# lamloei_node32s3wroom_ft231xq_main_2laye.net
KiCad netlist of a schematic drawn in EAGLE
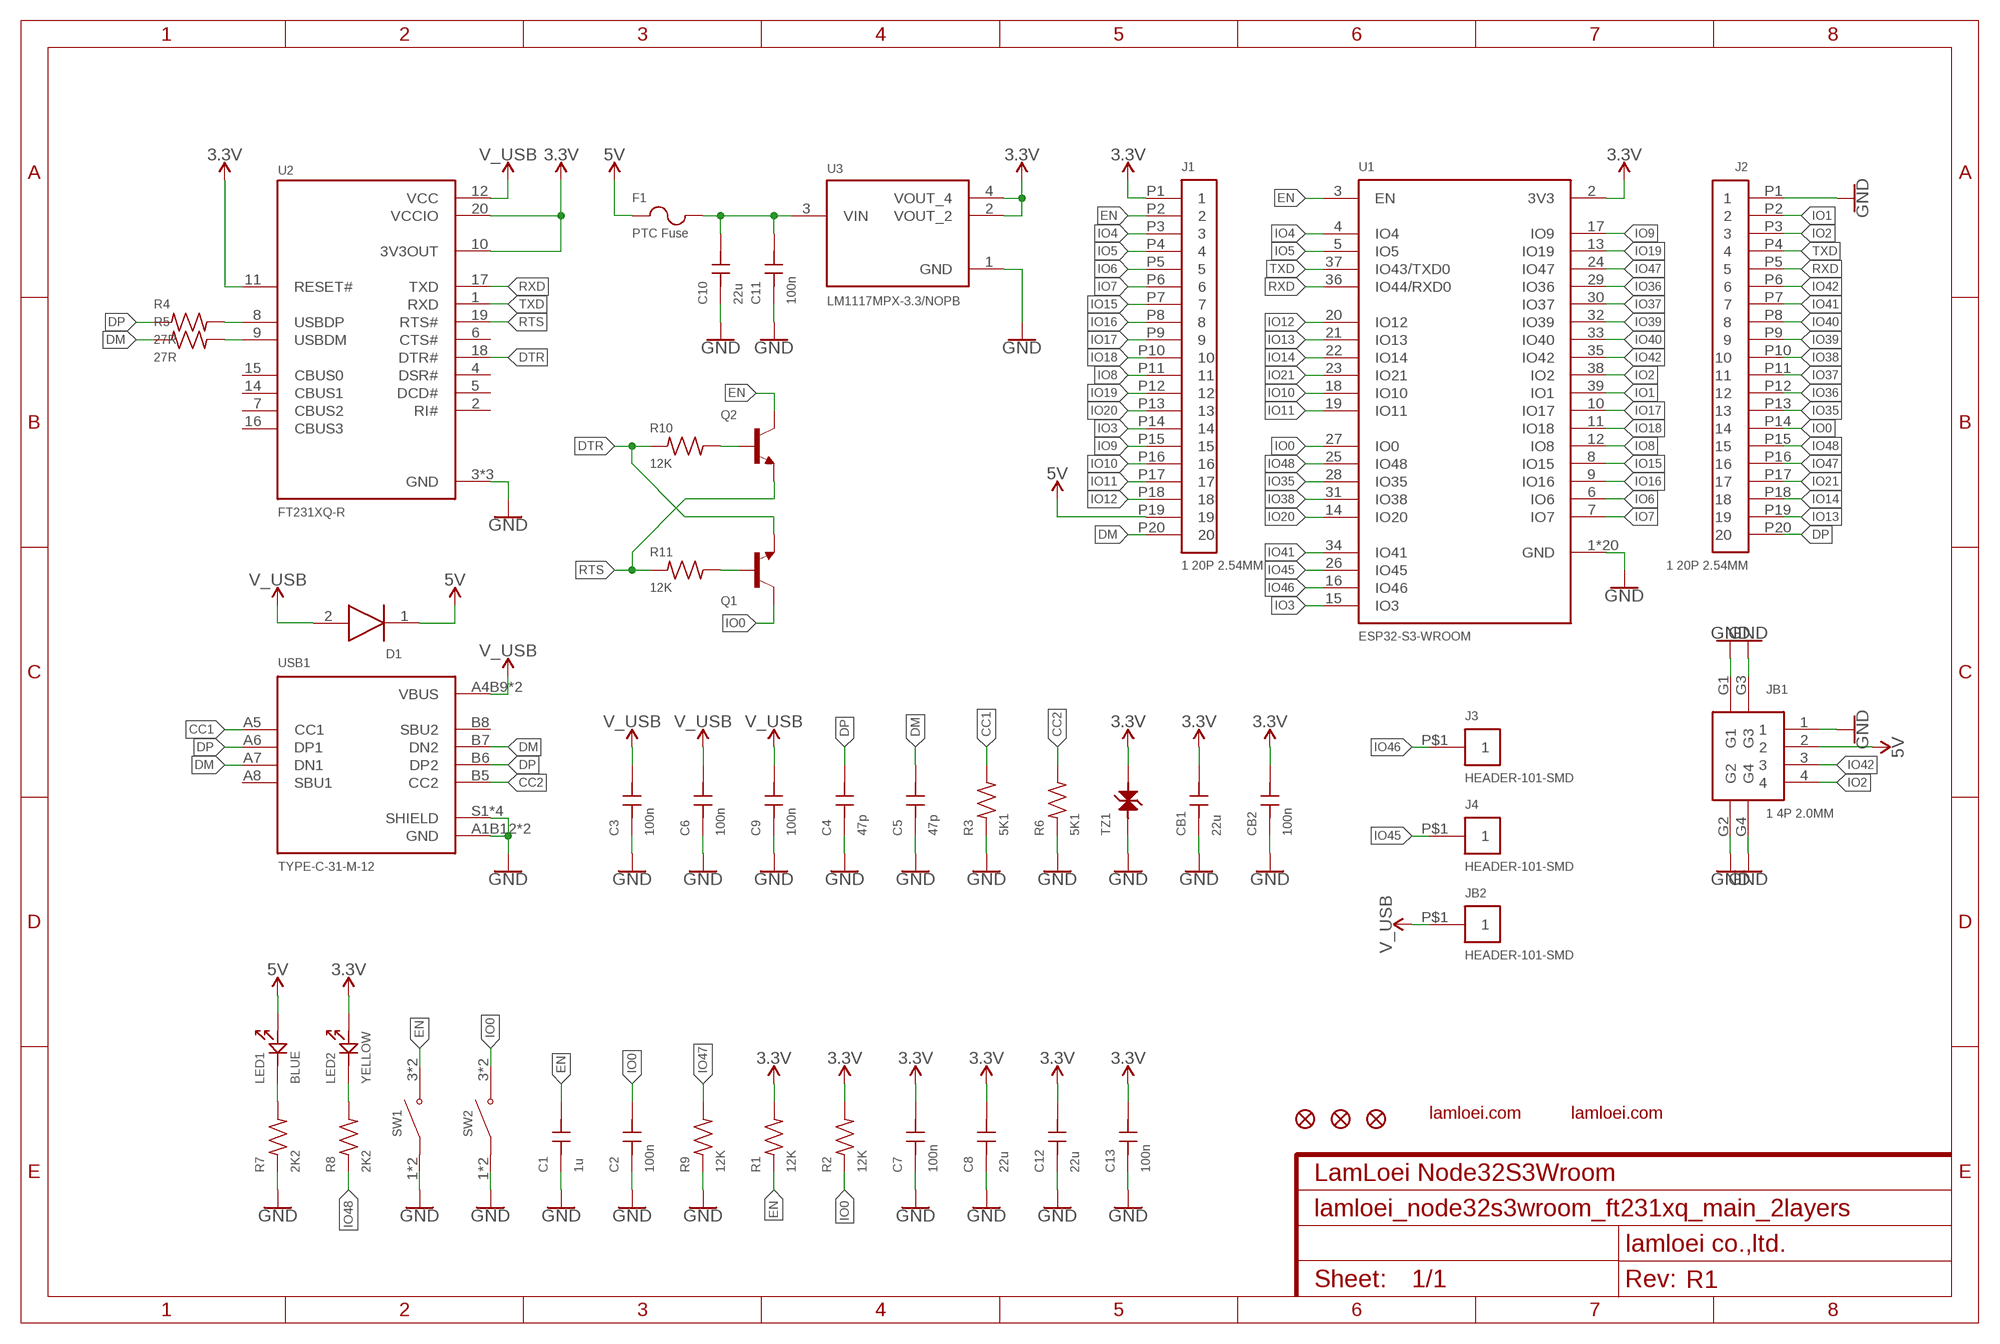
[diagram p0: schematic, sheet 1]

(export (version "E")
  (design (tool "Eeschema 10.0.6"))
  (components
    (comp (ref "C1")
      (value "1u")
      (footprint "eagle-import:GRM155R70J105KA12D")
      (fields (field (name "MANUFACTURER_PART_NUMBER") "GRM155R70J105KA12D"))
      (libsource (lib "eagle-import") (part "GRM155R70J105KA12D"))
    )
    (comp (ref "C2")
      (value "100n")
      (footprint "eagle-import:GCM155R71H104KE02D")
      (fields (field (name "MANUFACTURER_PART_NUMBER") "GCM155R71H104KE02D"))
      (libsource (lib "eagle-import") (part "GCM155R71H104KE02D"))
    )
    (comp (ref "C3")
      (value "100n")
      (footprint "eagle-import:GCM155R71H104KE02D")
      (fields (field (name "MANUFACTURER_PART_NUMBER") "GCM155R71H104KE02D"))
      (libsource (lib "eagle-import") (part "GCM155R71H104KE02D"))
    )
    (comp (ref "C4")
      (value "47p")
      (footprint "eagle-import:GCM1555C1H470JA16D")
      (fields (field (name "MANUFACTURER_PART_NUMBER") "GCM1555C1H470JA16D"))
      (libsource (lib "eagle-import") (part "GCM1555C1H470JA16D"))
    )
    (comp (ref "C5")
      (value "47p")
      (footprint "eagle-import:GCM1555C1H470JA16D")
      (fields (field (name "MANUFACTURER_PART_NUMBER") "GCM1555C1H470JA16D"))
      (libsource (lib "eagle-import") (part "GCM1555C1H470JA16D"))
    )
    (comp (ref "C6")
      (value "100n")
      (footprint "eagle-import:GCM155R71H104KE02D")
      (fields (field (name "MANUFACTURER_PART_NUMBER") "GCM155R71H104KE02D"))
      (libsource (lib "eagle-import") (part "GCM155R71H104KE02D"))
    )
    (comp (ref "C7")
      (value "100n")
      (footprint "eagle-import:GCM155R71H104KE02D")
      (fields (field (name "MANUFACTURER_PART_NUMBER") "GCM155R71H104KE02D"))
      (libsource (lib "eagle-import") (part "GCM155R71H104KE02D"))
    )
    (comp (ref "C8")
      (value "22u")
      (footprint "eagle-import:GCM21BR71H105KA03L")
      (fields (field (name "MANUFACTURER_PART_NUMBER") "GCM21BR71H105KA03L"))
      (libsource (lib "eagle-import") (part "GCM21BR71H105KA03L"))
    )
    (comp (ref "C9")
      (value "100n")
      (footprint "eagle-import:GCM155R71H104KE02D")
      (fields (field (name "MANUFACTURER_PART_NUMBER") "GCM155R71H104KE02D"))
      (libsource (lib "eagle-import") (part "GCM155R71H104KE02D"))
    )
    (comp (ref "C10")
      (value "22u")
      (footprint "eagle-import:GCM21BR71H105KA03L")
      (fields (field (name "MANUFACTURER_PART_NUMBER") "GCM21BR71H105KA03L"))
      (libsource (lib "eagle-import") (part "GCM21BR71H105KA03L"))
    )
    (comp (ref "C11")
      (value "100n")
      (footprint "eagle-import:GCM155R71H104KE02D")
      (fields (field (name "MANUFACTURER_PART_NUMBER") "GCM155R71H104KE02D"))
      (libsource (lib "eagle-import") (part "GCM155R71H104KE02D"))
    )
    (comp (ref "C12")
      (value "22u")
      (footprint "eagle-import:GCM21BR71H105KA03L")
      (fields (field (name "MANUFACTURER_PART_NUMBER") "GCM21BR71H105KA03L"))
      (libsource (lib "eagle-import") (part "GCM21BR71H105KA03L"))
    )
    (comp (ref "C13")
      (value "100n")
      (footprint "eagle-import:GCM155R71H104KE02D")
      (fields (field (name "MANUFACTURER_PART_NUMBER") "GCM155R71H104KE02D"))
      (libsource (lib "eagle-import") (part "GCM155R71H104KE02D"))
    )
    (comp (ref "CB1")
      (value "22u")
      (footprint "eagle-import:GCM21BR71H105KA03L")
      (fields (field (name "MANUFACTURER_PART_NUMBER") "GCM21BR71H105KA03L"))
      (libsource (lib "eagle-import") (part "GCM21BR71H105KA03L"))
    )
    (comp (ref "CB2")
      (value "100n")
      (footprint "eagle-import:GCM155R71H104KE02D")
      (fields (field (name "MANUFACTURER_PART_NUMBER") "GCM155R71H104KE02D"))
      (libsource (lib "eagle-import") (part "GCM155R71H104KE02D"))
    )
    (comp (ref "D1")
      (value "PMEG4050EP,115")
      (footprint "eagle-import:PMEG4050EP,115")
      (fields (field (name "RS_PART_NUMBER") "7805405P"))
      (libsource (lib "eagle-import") (part "PMEG4050EP,115"))
    )
    (comp (ref "F1")
      (value "PTC Fuse")
      (footprint "eagle-import:MF-NSMF050-2")
      (fields
        (field (name "LCSC_PART") "C75464")
        (field (name "MANUFACTURER") "BOURNS")
        (field (name "MANUFACTURER_PART_NUMBER") "MF-NSMF050-2")
      )
      (libsource (lib "eagle-import") (part "MF-NSMF050-2"))
    )
    (comp (ref "J1")
      (value "1 20P 2.54MM")
      (footprint "eagle-import:HEADER-120")
      (libsource (lib "eagle-import") (part "HEADER-120"))
    )
    (comp (ref "J2")
      (value "1 20P 2.54MM")
      (footprint "eagle-import:HEADER-120")
      (libsource (lib "eagle-import") (part "lamloei_e77_HEADER-120B_HEADER-120"))
    )
    (comp (ref "J3")
      (value "HEADER-101-SMD")
      (footprint "eagle-import:HEADER-101-SMD")
      (libsource (lib "eagle-import") (part "HEADER-101-SMD"))
    )
    (comp (ref "J4")
      (value "HEADER-101-SMD")
      (footprint "eagle-import:HEADER-101-SMD")
      (libsource (lib "eagle-import") (part "HEADER-101-SMD"))
    )
    (comp (ref "JB1")
      (value "1 4P 2.0MM")
      (footprint "eagle-import:A2012WR-S-4P")
      (libsource (lib "eagle-import") (part "A2012WR-S-4P"))
    )
    (comp (ref "JB2")
      (value "HEADER-101-SMD")
      (footprint "eagle-import:HEADER-101-SMD")
      (libsource (lib "eagle-import") (part "HEADER-101-SMD"))
    )
    (comp (ref "LED1")
      (value "BLUE")
      (footprint "eagle-import:19-217BHC-ZL1M2RY3T")
      (fields (field (name "MANUFACTURER_PART_NUMBER") "19-217BHC-ZL1M2RY3T"))
      (libsource (lib "eagle-import") (part "19-217BHC-ZL1M2RY3T"))
    )
    (comp (ref "LED2")
      (value "YELLOW")
      (footprint "eagle-import:19-213_Y2C-CQ2R2L_3T(CY)")
      (fields (field (name "MANUFACTURER_PART_NUMBER") "19-213/Y2C-CQ2R2L/3T(CY)"))
      (libsource (lib "eagle-import") (part "19-213/Y2C-CQ2R2L/3T(CY)"))
    )
    (comp (ref "Q1")
      (value "BC847B,215")
      (footprint "eagle-import:BC847B,215")
      (fields (field (name "MF") "ON Semiconductor") (field (name "MP") "BC847BLT3G"))
      (libsource (lib "eagle-import") (part "BC847B,215"))
    )
    (comp (ref "Q2")
      (value "BC847B,215")
      (footprint "eagle-import:BC847B,215")
      (fields (field (name "MF") "ON Semiconductor") (field (name "MP") "BC847BLT3G"))
      (libsource (lib "eagle-import") (part "BC847B,215"))
    )
    (comp (ref "R1")
      (value "12K")
      (footprint "eagle-import:R0402")
      (fields
        (field (name "LCSC_PART") "C114760")
        (field (name "MANUFACTURER") "YAGEO")
        (field (name "MANUFACTURER_PART_NUMBER") "RC0402FR-0712KL")
      )
      (libsource (lib "eagle-import") (part "RC0402FR-0712KL"))
    )
    (comp (ref "R2")
      (value "12K")
      (footprint "eagle-import:R0402")
      (fields
        (field (name "LCSC_PART") "C114760")
        (field (name "MANUFACTURER") "YAGEO")
        (field (name "MANUFACTURER_PART_NUMBER") "RC0402FR-0712KL")
      )
      (libsource (lib "eagle-import") (part "RC0402FR-0712KL"))
    )
    (comp (ref "R3")
      (value "5K1")
      (footprint "eagle-import:R0402")
      (fields
        (field (name "LCSC_PART") "C105872")
        (field (name "MANUFACTURER") "YAGEO")
        (field (name "MANUFACTURER_PART_NUMBER") "RC0402FR-075K1L")
      )
      (libsource (lib "eagle-import") (part "RC0402FR-075K1L"))
    )
    (comp (ref "R4")
      (value "27R")
      (footprint "eagle-import:R0402")
      (fields
        (field (name "LCSC_PART") "C138021")
        (field (name "MANUFACTURER") "YAGEO")
        (field (name "MANUFACTURER_PART_NUMBER") "RC0402FR-0727RL")
      )
      (libsource (lib "eagle-import") (part "RC0402FR-0727RL"))
    )
    (comp (ref "R5")
      (value "27R")
      (footprint "eagle-import:R0402")
      (fields
        (field (name "LCSC_PART") "C138021")
        (field (name "MANUFACTURER") "YAGEO")
        (field (name "MANUFACTURER_PART_NUMBER") "RC0402FR-0727RL")
      )
      (libsource (lib "eagle-import") (part "RC0402FR-0727RL"))
    )
    (comp (ref "R6")
      (value "5K1")
      (footprint "eagle-import:R0402")
      (fields
        (field (name "LCSC_PART") "C105872")
        (field (name "MANUFACTURER") "YAGEO")
        (field (name "MANUFACTURER_PART_NUMBER") "RC0402FR-075K1L")
      )
      (libsource (lib "eagle-import") (part "RC0402FR-075K1L"))
    )
    (comp (ref "R7")
      (value "2K2")
      (footprint "eagle-import:R0402")
      (fields
        (field (name "LCSC_PART") "C114762")
        (field (name "MANUFACTURER") "YAGEO")
        (field (name "MANUFACTURER_PART_NUMBER") "RC0402FR-072K2L")
      )
      (libsource (lib "eagle-import") (part "RC0402FR-072K2L"))
    )
    (comp (ref "R8")
      (value "2K2")
      (footprint "eagle-import:R0402")
      (fields
        (field (name "LCSC_PART") "C114762")
        (field (name "MANUFACTURER") "YAGEO")
        (field (name "MANUFACTURER_PART_NUMBER") "RC0402FR-072K2L")
      )
      (libsource (lib "eagle-import") (part "RC0402FR-072K2L"))
    )
    (comp (ref "R9")
      (value "12K")
      (footprint "eagle-import:R0402")
      (fields
        (field (name "LCSC_PART") "C114760")
        (field (name "MANUFACTURER") "YAGEO")
        (field (name "MANUFACTURER_PART_NUMBER") "RC0402FR-0712KL")
      )
      (libsource (lib "eagle-import") (part "RC0402FR-0712KL"))
    )
    (comp (ref "R10")
      (value "12K")
      (footprint "eagle-import:R0402")
      (fields
        (field (name "LCSC_PART") "C114760")
        (field (name "MANUFACTURER") "YAGEO")
        (field (name "MANUFACTURER_PART_NUMBER") "RC0402FR-0712KL")
      )
      (libsource (lib "eagle-import") (part "RC0402FR-0712KL"))
    )
    (comp (ref "R11")
      (value "12K")
      (footprint "eagle-import:R0402")
      (fields
        (field (name "LCSC_PART") "C114760")
        (field (name "MANUFACTURER") "YAGEO")
        (field (name "MANUFACTURER_PART_NUMBER") "RC0402FR-0712KL")
      )
      (libsource (lib "eagle-import") (part "RC0402FR-0712KL"))
    )
    (comp (ref "SW1")
      (value "K2-1808SN-A4SW-01")
      (footprint "eagle-import:K2-1808SN-A4SW-01")
      (fields (field (name "COMMENT") "4-1437565-2") (field (name "MF") "TE Connectivity"))
      (libsource (lib "eagle-import") (part "K2-1808SN-A4SW-01"))
    )
    (comp (ref "SW2")
      (value "K2-1808SN-A4SW-01")
      (footprint "eagle-import:K2-1808SN-A4SW-01")
      (fields (field (name "COMMENT") "4-1437565-2") (field (name "MF") "TE Connectivity"))
      (libsource (lib "eagle-import") (part "K2-1808SN-A4SW-01"))
    )
    (comp (ref "TZ1")
      (value "LXES15AAA1-153")
      (footprint "eagle-import:LXES15AAA1-153")
      (fields (field (name "LCSC_PART") "C86141") (field (name "MANUFACTURER") "Murata"))
      (libsource (lib "eagle-import") (part "LXES15AAA1-153"))
    )
    (comp (ref "U1")
      (value "ESP32-S3-WROOM")
      (footprint "eagle-import:ESP32-S3-WROOM")
      (fields (field (name "MF") "Olimex LTD") (field (name "MP") "ESP-WROOM-32"))
      (libsource (lib "eagle-import") (part "ESP32-S3-WROOM"))
    )
    (comp (ref "U2")
      (value "FT231XQ-R")
      (footprint "eagle-import:FT231XQ-R")
      (fields (field (name "MF") "FTDI, Future"))
      (libsource (lib "eagle-import") (part "FT231XQ-R"))
    )
    (comp (ref "U3")
      (value "LM1117MPX-3.3/NOPB")
      (footprint "eagle-import:LM1117MPX-3.3_NOPB")
      (fields (field (name "MF") "Texas Instruments"))
      (libsource (lib "eagle-import") (part "LM1117MPX-3.3/NOPB"))
    )
    (comp (ref "USB1")
      (value "TYPE-C-31-M-12")
      (footprint "eagle-import:TYPE-C-31-M-12")
      (fields (field (name "MF") "HRO Electronics Co., Ltd."))
      (libsource (lib "eagle-import") (part "TYPE-C-31-M-12"))
    )
    (comp (ref "ZFD1")
      (value "FIDUCIAL1X2")
      (footprint "eagle-import:FIDUCIAL-1X2")
      (libsource (lib "eagle-import") (part "FIDUCIAL1X2"))
    )
    (comp (ref "ZFD2")
      (value "FIDUCIAL1X2")
      (footprint "eagle-import:FIDUCIAL-1X2")
      (libsource (lib "eagle-import") (part "FIDUCIAL1X2"))
    )
    (comp (ref "ZFD3")
      (value "FIDUCIAL1X2")
      (footprint "eagle-import:FIDUCIAL-1X2")
      (libsource (lib "eagle-import") (part "FIDUCIAL1X2"))
    )
    (comp (ref "ZL1")
      (value "LAMLEOI_LOGO_3")
      (footprint "eagle-import:LAMLEOI_LOGO_3")
      (libsource (lib "eagle-import") (part "LAMLEOI_LOGO_3"))
    )
    (comp (ref "ZL2")
      (value "LAMLEOI_LOGO_3")
      (footprint "eagle-import:LAMLEOI_LOGO_3")
      (libsource (lib "eagle-import") (part "LAMLEOI_LOGO_3"))
    )
  )
  (nets
    (net (code "1") (name "3.3V") (class "Default")
      (node (ref "C12") (pin "2") (pinfunction "2_2") (pintype "passive"))
      (node (ref "C13") (pin "2") (pinfunction "2_2") (pintype "passive"))
      (node (ref "C7") (pin "2") (pinfunction "2_2") (pintype "passive"))
      (node (ref "C8") (pin "2") (pinfunction "2_2") (pintype "passive"))
      (node (ref "CB1") (pin "2") (pinfunction "2_2") (pintype "passive"))
      (node (ref "CB2") (pin "2") (pinfunction "2_2") (pintype "passive"))
      (node (ref "J1") (pin "P1") (pinfunction "1_P1") (pintype "passive"))
      (node (ref "LED2") (pin "2") (pinfunction "2_2") (pintype "passive"))
      (node (ref "R1") (pin "2") (pinfunction "2_2") (pintype "passive"))
      (node (ref "R2") (pin "2") (pinfunction "2_2") (pintype "passive"))
      (node (ref "TZ1") (pin "2") (pinfunction "2_2") (pintype "passive"))
      (node (ref "U1") (pin "2") (pinfunction "3V3_2") (pintype "power_in"))
      (node (ref "U2") (pin "10") (pinfunction "3V3OUT_10") (pintype "output"))
      (node (ref "U2") (pin "11") (pinfunction "RESET#_11") (pintype "input"))
      (node (ref "U2") (pin "20") (pinfunction "VCCIO_20") (pintype "power_in"))
      (node (ref "U3") (pin "2") (pinfunction "VOUT_2_2") (pintype "output"))
      (node (ref "U3") (pin "4") (pinfunction "VOUT_4_4") (pintype "output"))
    )
    (net (code "2") (name "5V") (class "Default")
      (node (ref "D1") (pin "1") (pinfunction "K_1") (pintype "bidirectional"))
      (node (ref "F1") (pin "1") (pinfunction "1_1") (pintype "passive"))
      (node (ref "J1") (pin "P19") (pinfunction "19_P19") (pintype "passive"))
      (node (ref "JB1") (pin "2") (pinfunction "2_2") (pintype "bidirectional"))
      (node (ref "LED1") (pin "2") (pinfunction "2_2") (pintype "passive"))
    )
    (net (code "3") (name "CC1") (class "Default")
      (node (ref "R3") (pin "2") (pinfunction "2_2") (pintype "passive"))
      (node (ref "USB1") (pin "A5") (pinfunction "CC1_A5") (pintype "bidirectional"))
    )
    (net (code "4") (name "CC2") (class "Default")
      (node (ref "R6") (pin "2") (pinfunction "2_2") (pintype "passive"))
      (node (ref "USB1") (pin "B5") (pinfunction "CC2_B5") (pintype "bidirectional"))
    )
    (net (code "5") (name "DM") (class "Default")
      (node (ref "C5") (pin "2") (pinfunction "2_2") (pintype "passive"))
      (node (ref "J1") (pin "P20") (pinfunction "20_P20") (pintype "passive"))
      (node (ref "R5") (pin "1") (pinfunction "1_1") (pintype "passive"))
      (node (ref "USB1") (pin "A7") (pinfunction "DN1_A7") (pintype "bidirectional"))
      (node (ref "USB1") (pin "B7") (pinfunction "DN2_B7") (pintype "bidirectional"))
    )
    (net (code "6") (name "DP") (class "Default")
      (node (ref "C4") (pin "2") (pinfunction "2_2") (pintype "passive"))
      (node (ref "J2") (pin "P20") (pinfunction "20_P20") (pintype "passive"))
      (node (ref "R4") (pin "1") (pinfunction "1_1") (pintype "passive"))
      (node (ref "USB1") (pin "A6") (pinfunction "DP1_A6") (pintype "bidirectional"))
      (node (ref "USB1") (pin "B6") (pinfunction "DP2_B6") (pintype "bidirectional"))
    )
    (net (code "7") (name "DTR") (class "Default")
      (node (ref "Q1") (pin "E") (pinfunction "E_E") (pintype "passive"))
      (node (ref "R10") (pin "1") (pinfunction "1_1") (pintype "passive"))
      (node (ref "U2") (pin "18") (pinfunction "DTR#_18") (pintype "output"))
    )
    (net (code "8") (name "EN") (class "Default")
      (node (ref "C1") (pin "2") (pinfunction "2_2") (pintype "passive"))
      (node (ref "J1") (pin "P2") (pinfunction "2_P2") (pintype "passive"))
      (node (ref "Q2") (pin "C") (pinfunction "C_C") (pintype "passive"))
      (node (ref "R1") (pin "1") (pinfunction "1_1") (pintype "passive"))
      (node (ref "SW1") (pin "3") (pinfunction "NO_3") (pintype "passive"))
      (node (ref "SW1") (pin "4") (pinfunction "NO_4") (pintype "passive"))
      (node (ref "U1") (pin "3") (pinfunction "EN_3") (pintype "input"))
    )
    (net (code "9") (name "GND") (class "Default")
      (node (ref "C1") (pin "1") (pinfunction "1_1") (pintype "passive"))
      (node (ref "C10") (pin "1") (pinfunction "1_1") (pintype "passive"))
      (node (ref "C11") (pin "1") (pinfunction "1_1") (pintype "passive"))
      (node (ref "C12") (pin "1") (pinfunction "1_1") (pintype "passive"))
      (node (ref "C13") (pin "1") (pinfunction "1_1") (pintype "passive"))
      (node (ref "C2") (pin "1") (pinfunction "1_1") (pintype "passive"))
      (node (ref "C3") (pin "1") (pinfunction "1_1") (pintype "passive"))
      (node (ref "C4") (pin "1") (pinfunction "1_1") (pintype "passive"))
      (node (ref "C5") (pin "1") (pinfunction "1_1") (pintype "passive"))
      (node (ref "C6") (pin "1") (pinfunction "1_1") (pintype "passive"))
      (node (ref "C7") (pin "1") (pinfunction "1_1") (pintype "passive"))
      (node (ref "C8") (pin "1") (pinfunction "1_1") (pintype "passive"))
      (node (ref "C9") (pin "1") (pinfunction "1_1") (pintype "passive"))
      (node (ref "CB1") (pin "1") (pinfunction "1_1") (pintype "passive"))
      (node (ref "CB2") (pin "1") (pinfunction "1_1") (pintype "passive"))
      (node (ref "J2") (pin "P1") (pinfunction "1_P1") (pintype "passive"))
      (node (ref "JB1") (pin "1") (pinfunction "1_1") (pintype "bidirectional"))
      (node (ref "JB1") (pin "G1") (pinfunction "G1_G1") (pintype "bidirectional"))
      (node (ref "JB1") (pin "G2") (pinfunction "G2_G2") (pintype "bidirectional"))
      (node (ref "JB1") (pin "G3") (pinfunction "G3_G3") (pintype "bidirectional"))
      (node (ref "JB1") (pin "G4") (pinfunction "G4_G4") (pintype "bidirectional"))
      (node (ref "R3") (pin "1") (pinfunction "1_1") (pintype "passive"))
      (node (ref "R6") (pin "1") (pinfunction "1_1") (pintype "passive"))
      (node (ref "R7") (pin "1") (pinfunction "1_1") (pintype "passive"))
      (node (ref "R9") (pin "1") (pinfunction "1_1") (pintype "passive"))
      (node (ref "SW1") (pin "1") (pinfunction "COM_1") (pintype "passive"))
      (node (ref "SW1") (pin "2") (pinfunction "COM_2") (pintype "passive"))
      (node (ref "SW2") (pin "1") (pinfunction "COM_1") (pintype "passive"))
      (node (ref "SW2") (pin "2") (pinfunction "COM_2") (pintype "passive"))
      (node (ref "TZ1") (pin "1") (pinfunction "1_1") (pintype "passive"))
      (node (ref "U1") (pin "1") (pinfunction "GND_1") (pintype "power_in"))
      (node (ref "U1") (pin "1.1") (pinfunction "GND_1.1") (pintype "power_in"))
      (node (ref "U1") (pin "1.10") (pinfunction "GND_1.10") (pintype "power_in"))
      (node (ref "U1") (pin "1.11") (pinfunction "GND_1.11") (pintype "power_in"))
      (node (ref "U1") (pin "1.12") (pinfunction "GND_1.12") (pintype "power_in"))
      (node (ref "U1") (pin "1.13") (pinfunction "GND_1.13") (pintype "power_in"))
      (node (ref "U1") (pin "1.14") (pinfunction "GND_1.14") (pintype "power_in"))
      (node (ref "U1") (pin "1.15") (pinfunction "GND_1.15") (pintype "power_in"))
      (node (ref "U1") (pin "1.16") (pinfunction "GND_1.16") (pintype "power_in"))
      (node (ref "U1") (pin "1.17") (pinfunction "GND_1.17") (pintype "power_in"))
      (node (ref "U1") (pin "1.18") (pinfunction "GND_1.18") (pintype "power_in"))
      (node (ref "U1") (pin "1.2") (pinfunction "GND_1.2") (pintype "power_in"))
      (node (ref "U1") (pin "1.3") (pinfunction "GND_1.3") (pintype "power_in"))
      (node (ref "U1") (pin "1.4") (pinfunction "GND_1.4") (pintype "power_in"))
      (node (ref "U1") (pin "1.5") (pinfunction "GND_1.5") (pintype "power_in"))
      (node (ref "U1") (pin "1.6") (pinfunction "GND_1.6") (pintype "power_in"))
      (node (ref "U1") (pin "1.7") (pinfunction "GND_1.7") (pintype "power_in"))
      (node (ref "U1") (pin "1.8") (pinfunction "GND_1.8") (pintype "power_in"))
      (node (ref "U1") (pin "1.9") (pinfunction "GND_1.9") (pintype "power_in"))
      (node (ref "U1") (pin "40") (pinfunction "GND_40") (pintype "power_in"))
      (node (ref "U2") (pin "13") (pinfunction "GND_13") (pintype "power_in"))
      (node (ref "U2") (pin "21") (pinfunction "GND_21") (pintype "power_in"))
      (node (ref "U2") (pin "3") (pinfunction "GND_3") (pintype "power_in"))
      (node (ref "U3") (pin "1") (pinfunction "GND_1") (pintype "power_in"))
      (node (ref "USB1") (pin "A1B12") (pinfunction "GND_A1B12") (pintype "power_in"))
      (node (ref "USB1") (pin "B1A12") (pinfunction "GND_B1A12") (pintype "power_in"))
      (node (ref "USB1") (pin "S1") (pinfunction "SHIELD_S1") (pintype "passive"))
      (node (ref "USB1") (pin "S2") (pinfunction "SHIELD_S2") (pintype "passive"))
      (node (ref "USB1") (pin "S3") (pinfunction "SHIELD_S3") (pintype "passive"))
      (node (ref "USB1") (pin "S4") (pinfunction "SHIELD_S4") (pintype "passive"))
    )
    (net (code "10") (name "IO0") (class "Default")
      (node (ref "C2") (pin "2") (pinfunction "2_2") (pintype "passive"))
      (node (ref "J2") (pin "P14") (pinfunction "14_P14") (pintype "passive"))
      (node (ref "Q1") (pin "C") (pinfunction "C_C") (pintype "passive"))
      (node (ref "R2") (pin "1") (pinfunction "1_1") (pintype "passive"))
      (node (ref "SW2") (pin "3") (pinfunction "NO_3") (pintype "passive"))
      (node (ref "SW2") (pin "4") (pinfunction "NO_4") (pintype "passive"))
      (node (ref "U1") (pin "27") (pinfunction "IO0_27") (pintype "bidirectional"))
    )
    (net (code "11") (name "IO1") (class "Default")
      (node (ref "J2") (pin "P2") (pinfunction "2_P2") (pintype "passive"))
      (node (ref "U1") (pin "39") (pinfunction "IO1_39") (pintype "bidirectional"))
    )
    (net (code "12") (name "IO2") (class "Default")
      (node (ref "J2") (pin "P3") (pinfunction "3_P3") (pintype "passive"))
      (node (ref "JB1") (pin "4") (pinfunction "4_4") (pintype "bidirectional"))
      (node (ref "U1") (pin "38") (pinfunction "IO2_38") (pintype "bidirectional"))
    )
    (net (code "13") (name "IO3") (class "Default")
      (node (ref "J1") (pin "P14") (pinfunction "14_P14") (pintype "passive"))
      (node (ref "U1") (pin "15") (pinfunction "IO3_15") (pintype "bidirectional"))
    )
    (net (code "14") (name "IO4") (class "Default")
      (node (ref "J1") (pin "P3") (pinfunction "3_P3") (pintype "passive"))
      (node (ref "U1") (pin "4") (pinfunction "IO4_4") (pintype "input"))
    )
    (net (code "15") (name "IO5") (class "Default")
      (node (ref "J1") (pin "P4") (pinfunction "4_P4") (pintype "passive"))
      (node (ref "U1") (pin "5") (pinfunction "IO5_5") (pintype "input"))
    )
    (net (code "16") (name "IO6") (class "Default")
      (node (ref "J1") (pin "P5") (pinfunction "5_P5") (pintype "passive"))
      (node (ref "U1") (pin "6") (pinfunction "IO6_6") (pintype "bidirectional"))
    )
    (net (code "17") (name "IO7") (class "Default")
      (node (ref "J1") (pin "P6") (pinfunction "6_P6") (pintype "passive"))
      (node (ref "U1") (pin "7") (pinfunction "IO7_7") (pintype "bidirectional"))
    )
    (net (code "18") (name "IO8") (class "Default")
      (node (ref "J1") (pin "P11") (pinfunction "11_P11") (pintype "passive"))
      (node (ref "U1") (pin "12") (pinfunction "IO8_12") (pintype "bidirectional"))
    )
    (net (code "19") (name "IO9") (class "Default")
      (node (ref "J1") (pin "P15") (pinfunction "15_P15") (pintype "passive"))
      (node (ref "U1") (pin "17") (pinfunction "IO9_17") (pintype "bidirectional"))
    )
    (net (code "20") (name "IO10") (class "Default")
      (node (ref "J1") (pin "P16") (pinfunction "16_P16") (pintype "passive"))
      (node (ref "U1") (pin "18") (pinfunction "IO10_18") (pintype "bidirectional"))
    )
    (net (code "21") (name "IO11") (class "Default")
      (node (ref "J1") (pin "P17") (pinfunction "17_P17") (pintype "passive"))
      (node (ref "U1") (pin "19") (pinfunction "IO11_19") (pintype "bidirectional"))
    )
    (net (code "22") (name "IO12") (class "Default")
      (node (ref "J1") (pin "P18") (pinfunction "18_P18") (pintype "passive"))
      (node (ref "U1") (pin "20") (pinfunction "IO12_20") (pintype "bidirectional"))
    )
    (net (code "23") (name "IO13") (class "Default")
      (node (ref "J2") (pin "P19") (pinfunction "19_P19") (pintype "passive"))
      (node (ref "U1") (pin "21") (pinfunction "IO13_21") (pintype "bidirectional"))
    )
    (net (code "24") (name "IO14") (class "Default")
      (node (ref "J2") (pin "P18") (pinfunction "18_P18") (pintype "passive"))
      (node (ref "U1") (pin "22") (pinfunction "IO14_22") (pintype "bidirectional"))
    )
    (net (code "25") (name "IO15") (class "Default")
      (node (ref "J1") (pin "P7") (pinfunction "7_P7") (pintype "passive"))
      (node (ref "U1") (pin "8") (pinfunction "IO15_8") (pintype "bidirectional"))
    )
    (net (code "26") (name "IO16") (class "Default")
      (node (ref "J1") (pin "P8") (pinfunction "8_P8") (pintype "passive"))
      (node (ref "U1") (pin "9") (pinfunction "IO16_9") (pintype "bidirectional"))
    )
    (net (code "27") (name "IO17") (class "Default")
      (node (ref "J1") (pin "P9") (pinfunction "9_P9") (pintype "passive"))
      (node (ref "U1") (pin "10") (pinfunction "IO17_10") (pintype "bidirectional"))
    )
    (net (code "28") (name "IO18") (class "Default")
      (node (ref "J1") (pin "P10") (pinfunction "10_P10") (pintype "passive"))
      (node (ref "U1") (pin "11") (pinfunction "IO18_11") (pintype "bidirectional"))
    )
    (net (code "29") (name "IO19") (class "Default")
      (node (ref "J1") (pin "P12") (pinfunction "12_P12") (pintype "passive"))
      (node (ref "U1") (pin "13") (pinfunction "IO19_13") (pintype "bidirectional"))
    )
    (net (code "30") (name "IO20") (class "Default")
      (node (ref "J1") (pin "P13") (pinfunction "13_P13") (pintype "passive"))
      (node (ref "U1") (pin "14") (pinfunction "IO20_14") (pintype "bidirectional"))
    )
    (net (code "31") (name "IO21") (class "Default")
      (node (ref "J2") (pin "P17") (pinfunction "17_P17") (pintype "passive"))
      (node (ref "U1") (pin "23") (pinfunction "IO21_23") (pintype "bidirectional"))
    )
    (net (code "32") (name "IO35") (class "Default")
      (node (ref "J2") (pin "P13") (pinfunction "13_P13") (pintype "passive"))
      (node (ref "U1") (pin "28") (pinfunction "IO35_28") (pintype "bidirectional"))
    )
    (net (code "33") (name "IO36") (class "Default")
      (node (ref "J2") (pin "P12") (pinfunction "12_P12") (pintype "passive"))
      (node (ref "U1") (pin "29") (pinfunction "IO36_29") (pintype "bidirectional"))
    )
    (net (code "34") (name "IO37") (class "Default")
      (node (ref "J2") (pin "P11") (pinfunction "11_P11") (pintype "passive"))
      (node (ref "U1") (pin "30") (pinfunction "IO37_30") (pintype "bidirectional"))
    )
    (net (code "35") (name "IO38") (class "Default")
      (node (ref "J2") (pin "P10") (pinfunction "10_P10") (pintype "passive"))
      (node (ref "U1") (pin "31") (pinfunction "IO38_31") (pintype "bidirectional"))
    )
    (net (code "36") (name "IO39") (class "Default")
      (node (ref "J2") (pin "P9") (pinfunction "9_P9") (pintype "passive"))
      (node (ref "U1") (pin "32") (pinfunction "IO39_32") (pintype "bidirectional"))
    )
    (net (code "37") (name "IO40") (class "Default")
      (node (ref "J2") (pin "P8") (pinfunction "8_P8") (pintype "passive"))
      (node (ref "U1") (pin "33") (pinfunction "IO40_33") (pintype "bidirectional"))
    )
    (net (code "38") (name "IO41") (class "Default")
      (node (ref "J2") (pin "P7") (pinfunction "7_P7") (pintype "passive"))
      (node (ref "U1") (pin "34") (pinfunction "IO41_34") (pintype "bidirectional"))
    )
    (net (code "39") (name "IO42") (class "Default")
      (node (ref "J2") (pin "P6") (pinfunction "6_P6") (pintype "passive"))
      (node (ref "JB1") (pin "3") (pinfunction "3_3") (pintype "bidirectional"))
      (node (ref "U1") (pin "35") (pinfunction "IO42_35") (pintype "bidirectional"))
    )
    (net (code "40") (name "IO45") (class "Default")
      (node (ref "J4") (pin "P$1") (pinfunction "1_P$1") (pintype "passive"))
      (node (ref "U1") (pin "26") (pinfunction "IO45_26") (pintype "bidirectional"))
    )
    (net (code "41") (name "IO46") (class "Default")
      (node (ref "J3") (pin "P$1") (pinfunction "1_P$1") (pintype "passive"))
      (node (ref "U1") (pin "16") (pinfunction "IO46_16") (pintype "bidirectional"))
    )
    (net (code "42") (name "IO47") (class "Default")
      (node (ref "J2") (pin "P16") (pinfunction "16_P16") (pintype "passive"))
      (node (ref "R9") (pin "2") (pinfunction "2_2") (pintype "passive"))
      (node (ref "U1") (pin "24") (pinfunction "IO47_24") (pintype "bidirectional"))
    )
    (net (code "43") (name "IO48") (class "Default")
      (node (ref "J2") (pin "P15") (pinfunction "15_P15") (pintype "passive"))
      (node (ref "R8") (pin "1") (pinfunction "1_1") (pintype "passive"))
      (node (ref "U1") (pin "25") (pinfunction "IO48_25") (pintype "bidirectional"))
    )
    (net (code "44") (name "Net-(LED1-Pad1)") (class "Default")
      (node (ref "LED1") (pin "1") (pinfunction "1_1") (pintype "passive"))
      (node (ref "R7") (pin "2") (pinfunction "2_2") (pintype "passive"))
    )
    (net (code "45") (name "Net-(LED2-Pad1)") (class "Default")
      (node (ref "LED2") (pin "1") (pinfunction "1_1") (pintype "passive"))
      (node (ref "R8") (pin "2") (pinfunction "2_2") (pintype "passive"))
    )
    (net (code "46") (name "Net-(Q1-PadB)") (class "Default")
      (node (ref "Q1") (pin "B") (pinfunction "B_B") (pintype "passive"))
      (node (ref "R11") (pin "2") (pinfunction "2_2") (pintype "passive"))
    )
    (net (code "47") (name "Net-(Q2-PadB)") (class "Default")
      (node (ref "Q2") (pin "B") (pinfunction "B_B") (pintype "passive"))
      (node (ref "R10") (pin "2") (pinfunction "2_2") (pintype "passive"))
    )
    (net (code "48") (name "Net-(U2-USBDM)") (class "Default")
      (node (ref "R5") (pin "2") (pinfunction "2_2") (pintype "passive"))
      (node (ref "U2") (pin "9") (pinfunction "USBDM_9") (pintype "bidirectional"))
    )
    (net (code "49") (name "Net-(U2-USBDP)") (class "Default")
      (node (ref "R4") (pin "2") (pinfunction "2_2") (pintype "passive"))
      (node (ref "U2") (pin "8") (pinfunction "USBDP_8") (pintype "bidirectional"))
    )
    (net (code "50") (name "Net-(U3-VIN)") (class "Default")
      (node (ref "C10") (pin "2") (pinfunction "2_2") (pintype "passive"))
      (node (ref "C11") (pin "2") (pinfunction "2_2") (pintype "passive"))
      (node (ref "F1") (pin "2") (pinfunction "2_2") (pintype "passive"))
      (node (ref "U3") (pin "3") (pinfunction "VIN_3") (pintype "input"))
    )
    (net (code "51") (name "RTS") (class "Default")
      (node (ref "Q2") (pin "E") (pinfunction "E_E") (pintype "passive"))
      (node (ref "R11") (pin "1") (pinfunction "1_1") (pintype "passive"))
      (node (ref "U2") (pin "19") (pinfunction "RTS#_19") (pintype "output"))
    )
    (net (code "52") (name "RXD") (class "Default")
      (node (ref "J2") (pin "P5") (pinfunction "5_P5") (pintype "passive"))
      (node (ref "U1") (pin "36") (pinfunction "IO44/RXD0_36") (pintype "bidirectional"))
      (node (ref "U2") (pin "17") (pinfunction "TXD_17") (pintype "output"))
    )
    (net (code "53") (name "TXD") (class "Default")
      (node (ref "J2") (pin "P4") (pinfunction "4_P4") (pintype "passive"))
      (node (ref "U1") (pin "37") (pinfunction "IO43/TXD0_37") (pintype "bidirectional"))
      (node (ref "U2") (pin "1") (pinfunction "RXD_1") (pintype "input"))
    )
    (net (code "54") (name "V_USB") (class "Default")
      (node (ref "C3") (pin "2") (pinfunction "2_2") (pintype "passive"))
      (node (ref "C6") (pin "2") (pinfunction "2_2") (pintype "passive"))
      (node (ref "C9") (pin "2") (pinfunction "2_2") (pintype "passive"))
      (node (ref "D1") (pin "2") (pinfunction "A_2") (pintype "bidirectional"))
      (node (ref "JB2") (pin "P$1") (pinfunction "1_P$1") (pintype "passive"))
      (node (ref "U2") (pin "12") (pinfunction "VCC_12") (pintype "power_in"))
      (node (ref "USB1") (pin "A4B9") (pinfunction "VBUS_A4B9") (pintype "power_in"))
      (node (ref "USB1") (pin "B4A9") (pinfunction "VBUS_B4A9") (pintype "power_in"))
    )
    (net (code "55") (name "unconnected-(U2-CBUS0-Pad15)") (class "Default")
      (node (ref "U2") (pin "15") (pinfunction "CBUS0_15") (pintype "bidirectional"))
    )
    (net (code "56") (name "unconnected-(U2-CBUS1-Pad14)") (class "Default")
      (node (ref "U2") (pin "14") (pinfunction "CBUS1_14") (pintype "bidirectional"))
    )
    (net (code "57") (name "unconnected-(U2-CBUS2-Pad7)") (class "Default")
      (node (ref "U2") (pin "7") (pinfunction "CBUS2_7") (pintype "bidirectional"))
    )
    (net (code "58") (name "unconnected-(U2-CBUS3-Pad16)") (class "Default")
      (node (ref "U2") (pin "16") (pinfunction "CBUS3_16") (pintype "bidirectional"))
    )
    (net (code "59") (name "unconnected-(U2-CTS#-Pad6)") (class "Default")
      (node (ref "U2") (pin "6") (pinfunction "CTS#_6") (pintype "input"))
    )
    (net (code "60") (name "unconnected-(U2-DCD#-Pad5)") (class "Default")
      (node (ref "U2") (pin "5") (pinfunction "DCD#_5") (pintype "input"))
    )
    (net (code "61") (name "unconnected-(U2-DSR#-Pad4)") (class "Default")
      (node (ref "U2") (pin "4") (pinfunction "DSR#_4") (pintype "input"))
    )
    (net (code "62") (name "unconnected-(U2-RI#-Pad2)") (class "Default")
      (node (ref "U2") (pin "2") (pinfunction "RI#_2") (pintype "input"))
    )
    (net (code "63") (name "unconnected-(USB1-SBU1-PadA8)") (class "Default")
      (node (ref "USB1") (pin "A8") (pinfunction "SBU1_A8") (pintype "bidirectional"))
    )
    (net (code "64") (name "unconnected-(USB1-SBU2-PadB8)") (class "Default")
      (node (ref "USB1") (pin "B8") (pinfunction "SBU2_B8") (pintype "bidirectional"))
    )
  )
)
